# ProtoTrinket.net
KiCad netlist of a schematic drawn in EAGLE
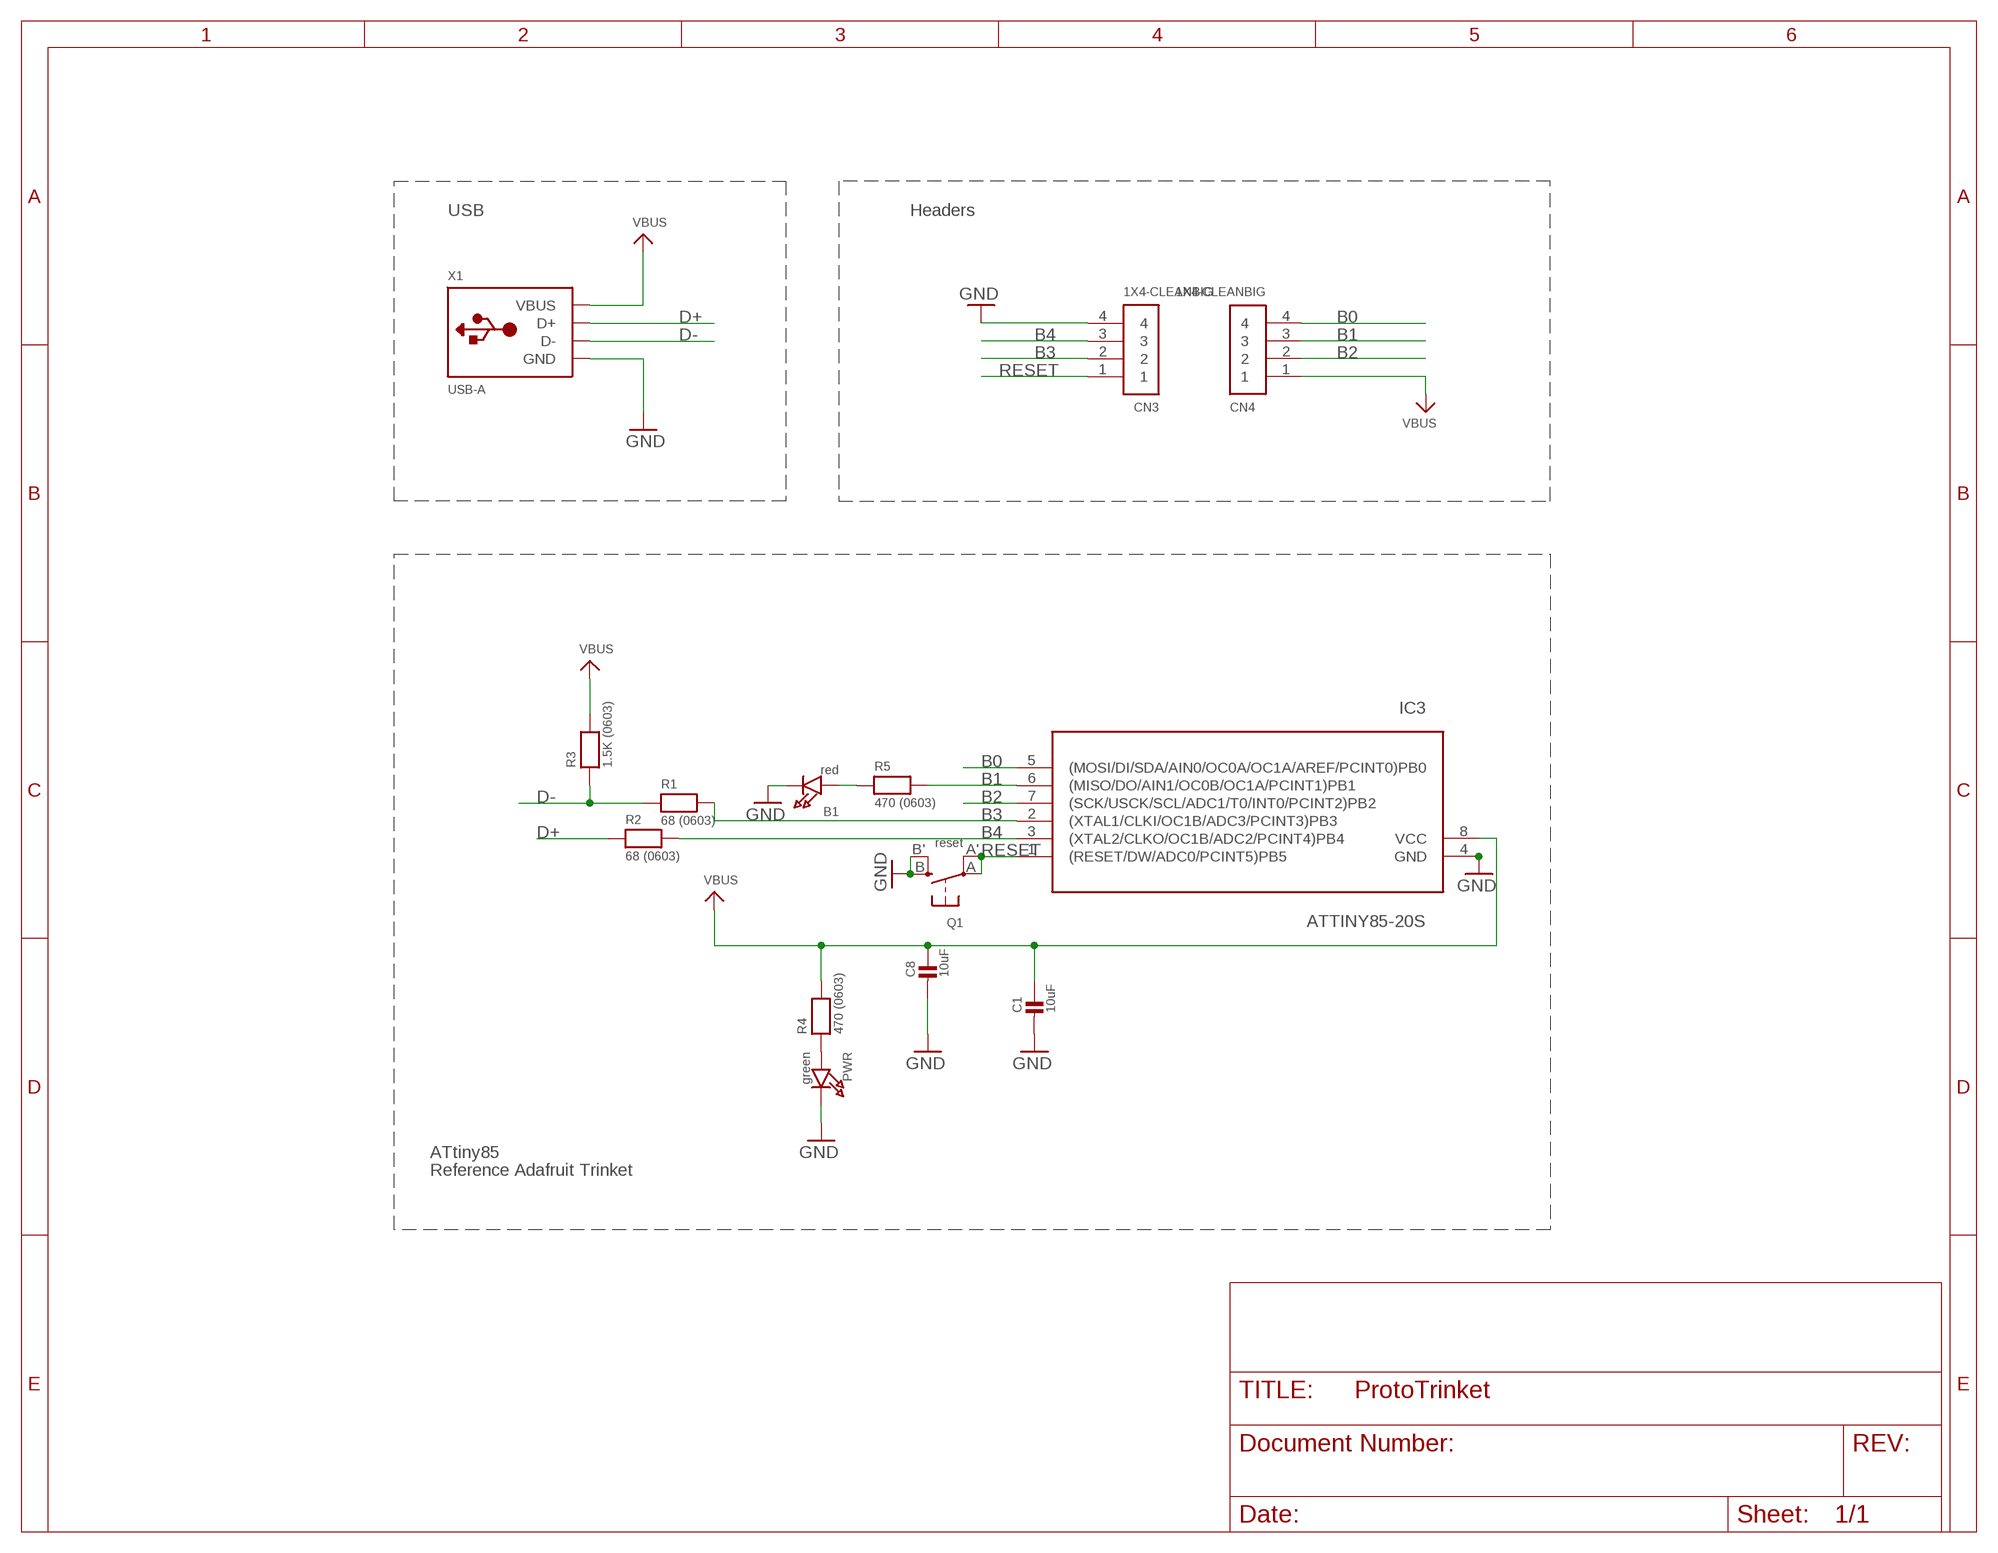
[diagram p0: schematic, sheet 1]

(export (version "E")
  (design (tool "Eeschema 10.0.6"))
  (components
    (comp (ref "B1")
      (value "red")
      (footprint "eagle-import:CHIPLED_0805_NOOUTLINE")
      (libsource (lib "eagle-import") (part "LED0805_NOOUTLINE"))
    )
    (comp (ref "C1")
      (value "10uF")
      (footprint "eagle-import:0805-NO")
      (libsource (lib "eagle-import") (part "CAP_CERAMIC0805-NOOUTLINE"))
    )
    (comp (ref "C8")
      (value "10uF")
      (footprint "eagle-import:0805-NO")
      (libsource (lib "eagle-import") (part "CAP_CERAMIC0805-NOOUTLINE"))
    )
    (comp (ref "CN3")
      (value "1X4-CLEANBIG")
      (footprint "eagle-import:1X04-CLEANBIG")
      (libsource (lib "eagle-import") (part "1X4-CLEANBIG"))
    )
    (comp (ref "CN4")
      (value "1X4-CLEANBIG")
      (footprint "eagle-import:1X04-CLEANBIG")
      (libsource (lib "eagle-import") (part "1X4-CLEANBIG"))
    )
    (comp (ref "IC3")
      (value "ATTINY85-20S")
      (footprint "eagle-import:SOIC8")
      (libsource (lib "eagle-import") (part "ATTINY85SV-10"))
    )
    (comp (ref "PWR")
      (value "green")
      (footprint "eagle-import:CHIPLED_0805_NOOUTLINE")
      (libsource (lib "eagle-import") (part "LED0805_NOOUTLINE"))
    )
    (comp (ref "Q1")
      (value "reset")
      (footprint "eagle-import:BTN_KMR2_4.6X2.8")
      (libsource (lib "eagle-import") (part "SWITCH_TACT_SMT4.6X2.8"))
    )
    (comp (ref "R1")
      (value "68 (0603)")
      (footprint "eagle-import:0603-NO")
      (libsource (lib "eagle-import") (part "RESISTOR_0603_NOOUT"))
    )
    (comp (ref "R2")
      (value "68 (0603)")
      (footprint "eagle-import:0603-NO")
      (libsource (lib "eagle-import") (part "RESISTOR_0603_NOOUT"))
    )
    (comp (ref "R3")
      (value "1.5K (0603)")
      (footprint "eagle-import:0603-NO")
      (libsource (lib "eagle-import") (part "RESISTOR_0603_NOOUT"))
    )
    (comp (ref "R4")
      (value "470 (0603)")
      (footprint "eagle-import:0603-NO")
      (libsource (lib "eagle-import") (part "RESISTOR_0603_NOOUT"))
    )
    (comp (ref "R5")
      (value "470 (0603)")
      (footprint "eagle-import:0603-NO")
      (libsource (lib "eagle-import") (part "RESISTOR_0603_NOOUT"))
    )
    (comp (ref "X1")
      (value "USB-A")
      (footprint "eagle-import:MOLEX_480371000")
      (libsource (lib "eagle-import") (part "USB-A"))
    )
  )
  (nets
    (net (code "1") (name "/B0") (class "Default")
      (node (ref "CN4") (pin "4") (pinfunction "4_4") (pintype "bidirectional"))
      (node (ref "IC3") (pin "5") (pinfunction "(MOSI/DI/SDA/AIN0/OC0A/OC1A/AREF/PCINT0)PB0_5") (pintype "bidirectional"))
    )
    (net (code "2") (name "/B1") (class "Default")
      (node (ref "CN4") (pin "3") (pinfunction "3_3") (pintype "bidirectional"))
      (node (ref "IC3") (pin "6") (pinfunction "(MISO/DO/AIN1/OC0B/OC1A/PCINT1)PB1_6") (pintype "bidirectional"))
      (node (ref "R5") (pin "2") (pinfunction "2_2") (pintype "passive"))
    )
    (net (code "3") (name "/B2") (class "Default")
      (node (ref "CN4") (pin "2") (pinfunction "2_2") (pintype "bidirectional"))
      (node (ref "IC3") (pin "7") (pinfunction "(SCK/USCK/SCL/ADC1/T0/INT0/PCINT2)PB2_7") (pintype "bidirectional"))
    )
    (net (code "4") (name "/B3") (class "Default")
      (node (ref "CN3") (pin "2") (pinfunction "2_2") (pintype "bidirectional"))
      (node (ref "IC3") (pin "2") (pinfunction "(XTAL1/CLKI/OC1B/ADC3/PCINT3)PB3_2") (pintype "bidirectional"))
      (node (ref "R1") (pin "2") (pinfunction "2_2") (pintype "passive"))
    )
    (net (code "5") (name "/B4") (class "Default")
      (node (ref "CN3") (pin "3") (pinfunction "3_3") (pintype "bidirectional"))
      (node (ref "IC3") (pin "3") (pinfunction "(XTAL2/CLKO/OC1B/ADC2/PCINT4)PB4_3") (pintype "bidirectional"))
      (node (ref "R2") (pin "2") (pinfunction "2_2") (pintype "passive"))
    )
    (net (code "6") (name "/D+") (class "Default")
      (node (ref "R2") (pin "1") (pinfunction "1_1") (pintype "passive"))
      (node (ref "X1") (pin "3") (pinfunction "D+_3") (pintype "bidirectional"))
    )
    (net (code "7") (name "/D-") (class "Default")
      (node (ref "R1") (pin "1") (pinfunction "1_1") (pintype "passive"))
      (node (ref "R3") (pin "1") (pinfunction "1_1") (pintype "passive"))
      (node (ref "X1") (pin "2") (pinfunction "D-_2") (pintype "bidirectional"))
    )
    (net (code "8") (name "/RESET") (class "Default")
      (node (ref "CN3") (pin "1") (pinfunction "1_1") (pintype "bidirectional"))
      (node (ref "IC3") (pin "1") (pinfunction "(RESET/DW/ADC0/PCINT5)PB5_1") (pintype "bidirectional"))
      (node (ref "Q1") (pin "A") (pinfunction "P_A") (pintype "passive"))
      (node (ref "Q1") (pin "A'") (pinfunction "P1_A'") (pintype "passive"))
    )
    (net (code "9") (name "GND") (class "Default")
      (node (ref "B1") (pin "C") (pinfunction "C_C") (pintype "passive"))
      (node (ref "C1") (pin "2") (pinfunction "2_2") (pintype "passive"))
      (node (ref "C8") (pin "2") (pinfunction "2_2") (pintype "passive"))
      (node (ref "CN3") (pin "4") (pinfunction "4_4") (pintype "bidirectional"))
      (node (ref "IC3") (pin "4") (pinfunction "GND_4") (pintype "bidirectional"))
      (node (ref "PWR") (pin "C") (pinfunction "C_C") (pintype "passive"))
      (node (ref "Q1") (pin "B") (pinfunction "S_B") (pintype "passive"))
      (node (ref "Q1") (pin "B'") (pinfunction "S1_B'") (pintype "passive"))
      (node (ref "X1") (pin "4") (pinfunction "GND_4") (pintype "power_in"))
    )
    (net (code "10") (name "Net-(B1-PadA)") (class "Default")
      (node (ref "B1") (pin "A") (pinfunction "A_A") (pintype "passive"))
      (node (ref "R5") (pin "1") (pinfunction "1_1") (pintype "passive"))
    )
    (net (code "11") (name "Net-(PWR-PadA)") (class "Default")
      (node (ref "PWR") (pin "A") (pinfunction "A_A") (pintype "passive"))
      (node (ref "R4") (pin "1") (pinfunction "1_1") (pintype "passive"))
    )
    (net (code "12") (name "VBUS") (class "Default")
      (node (ref "C1") (pin "1") (pinfunction "1_1") (pintype "passive"))
      (node (ref "C8") (pin "1") (pinfunction "1_1") (pintype "passive"))
      (node (ref "CN4") (pin "1") (pinfunction "1_1") (pintype "bidirectional"))
      (node (ref "IC3") (pin "8") (pinfunction "VCC_8") (pintype "bidirectional"))
      (node (ref "R3") (pin "2") (pinfunction "2_2") (pintype "passive"))
      (node (ref "R4") (pin "2") (pinfunction "2_2") (pintype "passive"))
      (node (ref "X1") (pin "1") (pinfunction "VBUS_1") (pintype "power_in"))
    )
  )
)
